# PS2.net
KiCad netlist of a schematic drawn in Altium Designer
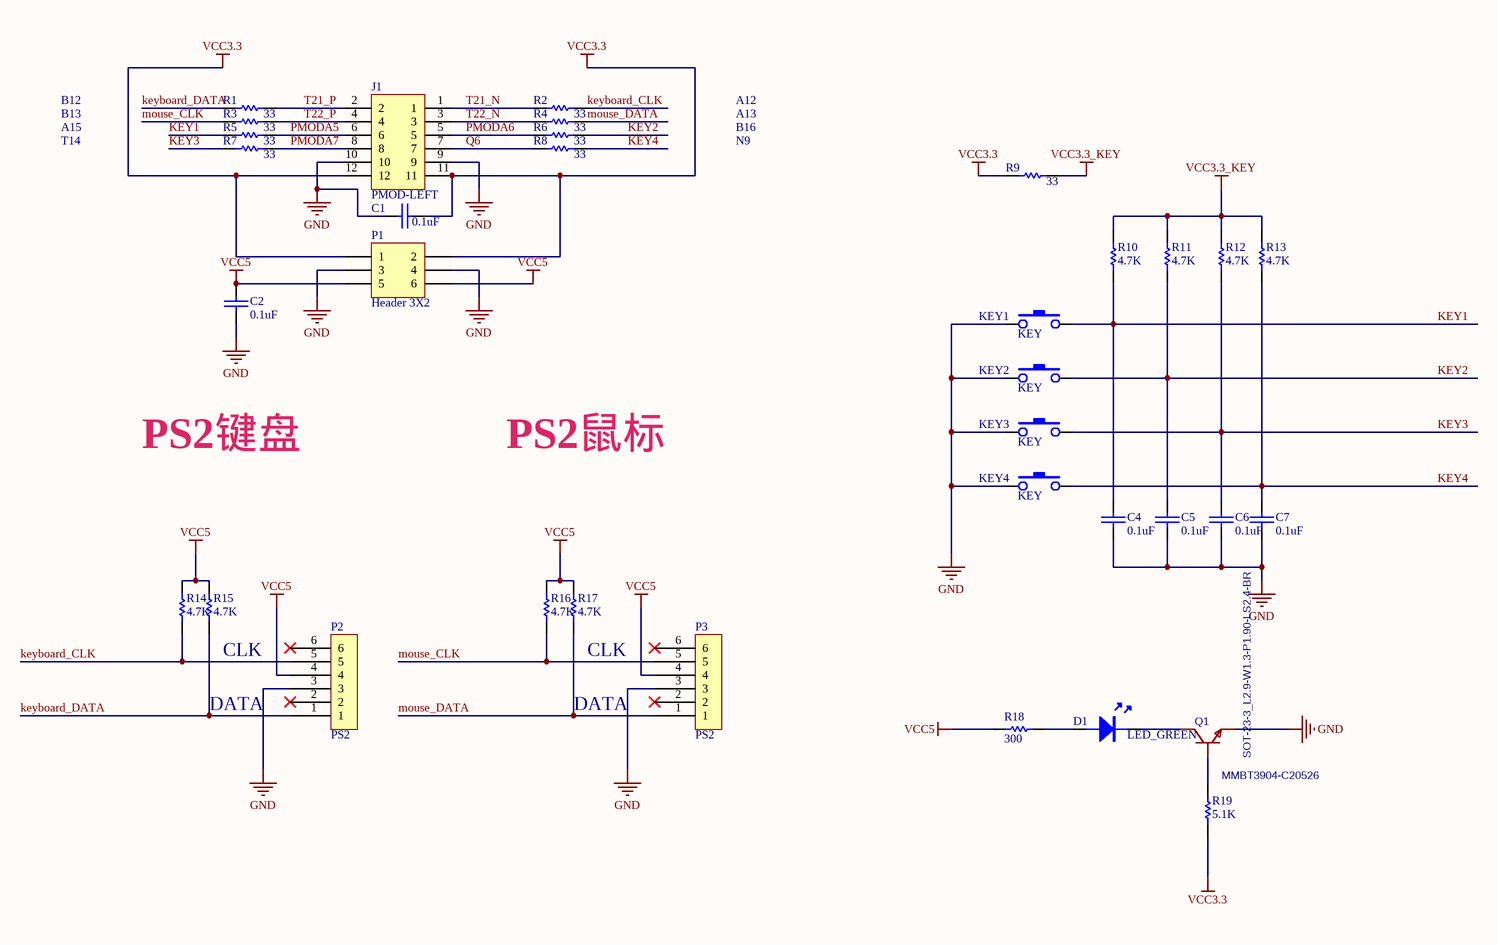
[diagram p0: PS2.SchDoc]

(export (version "E")
  (design (tool "Eeschema 10.0.6"))
  (components
    (comp (ref "C1")
      (value "0.1uF")
      (footprint "0603C")
      (description "无极性电容")
      (libsource (lib "电容") (part "CAP"))
    )
    (comp (ref "C2")
      (value "0.1uF")
      (footprint "0603C")
      (description "无极性电容")
      (libsource (lib "电容") (part "CAP"))
    )
    (comp (ref "C4")
      (value "0.1uF")
      (footprint "0603C")
      (description "无极性电容")
      (libsource (lib "电容") (part "CAP"))
    )
    (comp (ref "C5")
      (value "0.1uF")
      (footprint "0603C")
      (description "无极性电容")
      (libsource (lib "电容") (part "CAP"))
    )
    (comp (ref "C6")
      (value "0.1uF")
      (footprint "0603C")
      (description "无极性电容")
      (libsource (lib "电容") (part "CAP"))
    )
    (comp (ref "C7")
      (value "0.1uF")
      (footprint "0603C")
      (description "无极性电容")
      (libsource (lib "电容") (part "CAP"))
    )
    (comp (ref "D1") (value "LED_GREEN") (footprint "LED-0603G") (libsource (lib "LED") (part "LED")))
    (comp (ref "J1")
      (value "PMOD-LEFT")
      (footprint "2X6P RIGHT")
      (libsource (lib "排母") (part "Female HDR2X6"))
    )
    (comp (ref "KEY1") (value "KEY") (footprint "SMD-3X6X2.5") (libsource (lib "轻触开关") (part "KEY")))
    (comp (ref "KEY2") (value "KEY") (footprint "SMD-3X6X2.5") (libsource (lib "轻触开关") (part "KEY")))
    (comp (ref "KEY3") (value "KEY") (footprint "SMD-3X6X2.5") (libsource (lib "轻触开关") (part "KEY")))
    (comp (ref "KEY4") (value "KEY") (footprint "SMD-3X6X2.5") (libsource (lib "轻触开关") (part "KEY")))
    (comp (ref "P1")
      (value "Header 3X2")
      (footprint "HDR2X3")
      (description "Header, 3-Pin, Dual row")
      (fields (field (name "PUBLISHER") "Altium Limited"))
      (libsource (lib "Miscellaneous Connectors") (part "Header 3X2"))
    )
    (comp (ref "P2") (value "PS2") (footprint "PS2") (libsource (lib "the_god_of_death") (part "PS2")))
    (comp (ref "P3") (value "PS2") (footprint "PS2") (libsource (lib "the_god_of_death") (part "PS2")))
    (comp (ref "Q1")
      (value "MMBT3904-C20526")
      (footprint "SOT-23-3_L2.9-W1.3-P1.90-LS2.4-BR")
      (fields
        (field (name "BOM_MANUFACTURER PART") "MMBT3904")
        (field (name "BOM_SUPPLIER PART") "C20526")
        (field (name "CONTRIBUTOR") "立创EDA官方封装库")
      )
      (libsource (lib "altium-import") (part "root_1_MMBT3904-C20526_"))
    )
    (comp (ref "R1") (value "33") (footprint "0603_Q0603A") (libsource (lib "the_god_of_death") (part "RES")))
    (comp (ref "R2") (value "33") (footprint "0603_Q0603A") (libsource (lib "the_god_of_death") (part "RES")))
    (comp (ref "R3") (value "33") (footprint "0603_Q0603A") (libsource (lib "the_god_of_death") (part "RES")))
    (comp (ref "R4") (value "33") (footprint "0603_Q0603A") (libsource (lib "the_god_of_death") (part "RES")))
    (comp (ref "R5") (value "33") (footprint "0603_Q0603A") (libsource (lib "the_god_of_death") (part "RES")))
    (comp (ref "R6") (value "33") (footprint "0603_Q0603A") (libsource (lib "the_god_of_death") (part "RES")))
    (comp (ref "R7") (value "33") (footprint "0603_Q0603A") (libsource (lib "the_god_of_death") (part "RES")))
    (comp (ref "R8") (value "33") (footprint "0603_Q0603A") (libsource (lib "the_god_of_death") (part "RES")))
    (comp (ref "R9") (value "33") (footprint "0603_Q0603A") (libsource (lib "the_god_of_death") (part "RES")))
    (comp (ref "R10")
      (value "4.7K")
      (footprint "0603_Q0603A")
      (libsource (lib "the_god_of_death") (part "RES"))
    )
    (comp (ref "R11")
      (value "4.7K")
      (footprint "0603_Q0603A")
      (libsource (lib "the_god_of_death") (part "RES"))
    )
    (comp (ref "R12")
      (value "4.7K")
      (footprint "0603_Q0603A")
      (libsource (lib "the_god_of_death") (part "RES"))
    )
    (comp (ref "R13")
      (value "4.7K")
      (footprint "0603_Q0603A")
      (libsource (lib "the_god_of_death") (part "RES"))
    )
    (comp (ref "R14")
      (value "4.7K")
      (footprint "0603_Q0603A")
      (libsource (lib "the_god_of_death") (part "RES"))
    )
    (comp (ref "R15")
      (value "4.7K")
      (footprint "0603_Q0603A")
      (libsource (lib "the_god_of_death") (part "RES"))
    )
    (comp (ref "R16")
      (value "4.7K")
      (footprint "0603_Q0603A")
      (libsource (lib "the_god_of_death") (part "RES"))
    )
    (comp (ref "R17")
      (value "4.7K")
      (footprint "0603_Q0603A")
      (libsource (lib "the_god_of_death") (part "RES"))
    )
    (comp (ref "R18")
      (value "300")
      (footprint "0603_Q0603A")
      (libsource (lib "the_god_of_death") (part "RES"))
    )
    (comp (ref "R19") (value "5.1K") (footprint "0603_Q0603A") (libsource (lib "电阻") (part "RES")))
  )
  (nets
    (net (code "1") (name "/KEY1") (class "Default")
      (node (ref "C4") (pin "2") (pinfunction "2_2") (pintype "passive"))
      (node (ref "KEY1") (pin "3") (pinfunction "3_3") (pintype "passive"))
      (node (ref "R10") (pin "1") (pinfunction "1_1") (pintype "passive"))
      (node (ref "R5") (pin "1") (pinfunction "1_1") (pintype "passive"))
    )
    (net (code "2") (name "/KEY2") (class "Default")
      (node (ref "C5") (pin "2") (pinfunction "2_2") (pintype "passive"))
      (node (ref "KEY2") (pin "3") (pinfunction "3_3") (pintype "passive"))
      (node (ref "R11") (pin "1") (pinfunction "1_1") (pintype "passive"))
      (node (ref "R6") (pin "2") (pinfunction "2_2") (pintype "passive"))
    )
    (net (code "3") (name "/KEY3") (class "Default")
      (node (ref "C6") (pin "2") (pinfunction "2_2") (pintype "passive"))
      (node (ref "KEY3") (pin "3") (pinfunction "3_3") (pintype "passive"))
      (node (ref "R12") (pin "1") (pinfunction "1_1") (pintype "passive"))
      (node (ref "R7") (pin "1") (pinfunction "1_1") (pintype "passive"))
    )
    (net (code "4") (name "/KEY4") (class "Default")
      (node (ref "C7") (pin "2") (pinfunction "2_2") (pintype "passive"))
      (node (ref "KEY4") (pin "3") (pinfunction "3_3") (pintype "passive"))
      (node (ref "R13") (pin "1") (pinfunction "1_1") (pintype "passive"))
      (node (ref "R8") (pin "2") (pinfunction "2_2") (pintype "passive"))
    )
    (net (code "5") (name "/PMODA5") (class "Default")
      (node (ref "J1") (pin "6") (pinfunction "6_6") (pintype "passive"))
      (node (ref "R5") (pin "2") (pinfunction "2_2") (pintype "passive"))
    )
    (net (code "6") (name "/PMODA6") (class "Default")
      (node (ref "J1") (pin "5") (pinfunction "5_5") (pintype "passive"))
      (node (ref "R6") (pin "1") (pinfunction "1_1") (pintype "passive"))
    )
    (net (code "7") (name "/PMODA7") (class "Default")
      (node (ref "J1") (pin "8") (pinfunction "8_8") (pintype "passive"))
      (node (ref "R7") (pin "2") (pinfunction "2_2") (pintype "passive"))
    )
    (net (code "8") (name "/Q6") (class "Default")
      (node (ref "J1") (pin "7") (pinfunction "7_7") (pintype "passive"))
      (node (ref "R8") (pin "1") (pinfunction "1_1") (pintype "passive"))
    )
    (net (code "9") (name "/T21_N") (class "Default")
      (node (ref "J1") (pin "1") (pinfunction "1_1") (pintype "passive"))
      (node (ref "R2") (pin "1") (pinfunction "1_1") (pintype "passive"))
    )
    (net (code "10") (name "/T21_P") (class "Default")
      (node (ref "J1") (pin "2") (pinfunction "2_2") (pintype "passive"))
      (node (ref "R1") (pin "2") (pinfunction "2_2") (pintype "passive"))
    )
    (net (code "11") (name "/T22_N") (class "Default")
      (node (ref "J1") (pin "3") (pinfunction "3_3") (pintype "passive"))
      (node (ref "R4") (pin "1") (pinfunction "1_1") (pintype "passive"))
    )
    (net (code "12") (name "/T22_P") (class "Default")
      (node (ref "J1") (pin "4") (pinfunction "4_4") (pintype "passive"))
      (node (ref "R3") (pin "2") (pinfunction "2_2") (pintype "passive"))
    )
    (net (code "13") (name "/keyboard_CLK") (class "Default")
      (node (ref "P2") (pin "5") (pinfunction "5_5") (pintype "passive"))
      (node (ref "R14") (pin "1") (pinfunction "1_1") (pintype "passive"))
      (node (ref "R2") (pin "2") (pinfunction "2_2") (pintype "passive"))
    )
    (net (code "14") (name "/keyboard_DATA") (class "Default")
      (node (ref "P2") (pin "1") (pinfunction "1_1") (pintype "passive"))
      (node (ref "R1") (pin "1") (pinfunction "1_1") (pintype "passive"))
      (node (ref "R15") (pin "1") (pinfunction "1_1") (pintype "passive"))
    )
    (net (code "15") (name "/mouse_CLK") (class "Default")
      (node (ref "P3") (pin "5") (pinfunction "5_5") (pintype "passive"))
      (node (ref "R16") (pin "1") (pinfunction "1_1") (pintype "passive"))
      (node (ref "R3") (pin "1") (pinfunction "1_1") (pintype "passive"))
    )
    (net (code "16") (name "/mouse_DATA") (class "Default")
      (node (ref "P3") (pin "1") (pinfunction "1_1") (pintype "passive"))
      (node (ref "R17") (pin "1") (pinfunction "1_1") (pintype "passive"))
      (node (ref "R4") (pin "2") (pinfunction "2_2") (pintype "passive"))
    )
    (net (code "17") (name "GND") (class "Default")
      (node (ref "C1") (pin "1") (pinfunction "1_1") (pintype "passive"))
      (node (ref "C2") (pin "1") (pinfunction "1_1") (pintype "passive"))
      (node (ref "C4") (pin "1") (pinfunction "1_1") (pintype "passive"))
      (node (ref "C5") (pin "1") (pinfunction "1_1") (pintype "passive"))
      (node (ref "C6") (pin "1") (pinfunction "1_1") (pintype "passive"))
      (node (ref "C7") (pin "1") (pinfunction "1_1") (pintype "passive"))
      (node (ref "J1") (pin "10") (pinfunction "10_10") (pintype "passive"))
      (node (ref "J1") (pin "9") (pinfunction "9_9") (pintype "passive"))
      (node (ref "KEY1") (pin "1") (pinfunction "1_1") (pintype "passive"))
      (node (ref "KEY2") (pin "1") (pinfunction "1_1") (pintype "passive"))
      (node (ref "KEY3") (pin "1") (pinfunction "1_1") (pintype "passive"))
      (node (ref "KEY4") (pin "1") (pinfunction "1_1") (pintype "passive"))
      (node (ref "P1") (pin "3") (pinfunction "3_3") (pintype "passive"))
      (node (ref "P1") (pin "4") (pinfunction "4_4") (pintype "passive"))
      (node (ref "P2") (pin "3") (pinfunction "3_3") (pintype "passive"))
      (node (ref "P3") (pin "3") (pinfunction "3_3") (pintype "passive"))
      (node (ref "Q1") (pin "2") (pinfunction "E_2") (pintype "passive"))
    )
    (net (code "18") (name "Net-(D1-PadA)") (class "Default")
      (node (ref "D1") (pin "A") (pinfunction "A_A") (pintype "passive"))
      (node (ref "R18") (pin "2") (pinfunction "2_2") (pintype "passive"))
    )
    (net (code "19") (name "Net-(Q1-B)") (class "Default")
      (node (ref "Q1") (pin "1") (pinfunction "B_1") (pintype "passive"))
      (node (ref "R19") (pin "2") (pinfunction "2_2") (pintype "passive"))
    )
    (net (code "20") (name "Net-(Q1-C)") (class "Default")
      (node (ref "D1") (pin "K") (pinfunction "K_K") (pintype "passive"))
      (node (ref "Q1") (pin "3") (pinfunction "C_3") (pintype "passive"))
    )
    (net (code "21") (name "VCC3.3") (class "Default")
      (node (ref "C1") (pin "2") (pinfunction "2_2") (pintype "passive"))
      (node (ref "J1") (pin "11") (pinfunction "11_11") (pintype "passive"))
      (node (ref "J1") (pin "12") (pinfunction "12_12") (pintype "passive"))
      (node (ref "P1") (pin "1") (pinfunction "1_1") (pintype "passive"))
      (node (ref "P1") (pin "2") (pinfunction "2_2") (pintype "passive"))
      (node (ref "R19") (pin "1") (pinfunction "1_1") (pintype "passive"))
      (node (ref "R9") (pin "1") (pinfunction "1_1") (pintype "passive"))
    )
    (net (code "22") (name "VCC3.3_KEY") (class "Default")
      (node (ref "R10") (pin "2") (pinfunction "2_2") (pintype "passive"))
      (node (ref "R11") (pin "2") (pinfunction "2_2") (pintype "passive"))
      (node (ref "R12") (pin "2") (pinfunction "2_2") (pintype "passive"))
      (node (ref "R13") (pin "2") (pinfunction "2_2") (pintype "passive"))
      (node (ref "R9") (pin "2") (pinfunction "2_2") (pintype "passive"))
    )
    (net (code "23") (name "VCC5") (class "Default")
      (node (ref "C2") (pin "2") (pinfunction "2_2") (pintype "passive"))
      (node (ref "P1") (pin "5") (pinfunction "5_5") (pintype "passive"))
      (node (ref "P1") (pin "6") (pinfunction "6_6") (pintype "passive"))
      (node (ref "P2") (pin "4") (pinfunction "4_4") (pintype "passive"))
      (node (ref "P3") (pin "4") (pinfunction "4_4") (pintype "passive"))
      (node (ref "R14") (pin "2") (pinfunction "2_2") (pintype "passive"))
      (node (ref "R15") (pin "2") (pinfunction "2_2") (pintype "passive"))
      (node (ref "R16") (pin "2") (pinfunction "2_2") (pintype "passive"))
      (node (ref "R17") (pin "2") (pinfunction "2_2") (pintype "passive"))
      (node (ref "R18") (pin "1") (pinfunction "1_1") (pintype "passive"))
    )
    (net (code "24") (name "unconnected-(P2-Pad2)") (class "Default")
      (node (ref "P2") (pin "2") (pinfunction "2_2") (pintype "passive+no_connect"))
    )
    (net (code "25") (name "unconnected-(P2-Pad6)") (class "Default")
      (node (ref "P2") (pin "6") (pinfunction "6_6") (pintype "passive+no_connect"))
    )
    (net (code "26") (name "unconnected-(P3-Pad2)") (class "Default")
      (node (ref "P3") (pin "2") (pinfunction "2_2") (pintype "passive+no_connect"))
    )
    (net (code "27") (name "unconnected-(P3-Pad6)") (class "Default")
      (node (ref "P3") (pin "6") (pinfunction "6_6") (pintype "passive+no_connect"))
    )
  )
)
